# RPI_Pico_Breakout_2021-05-18.net
KiCad netlist of a schematic drawn in EasyEDA
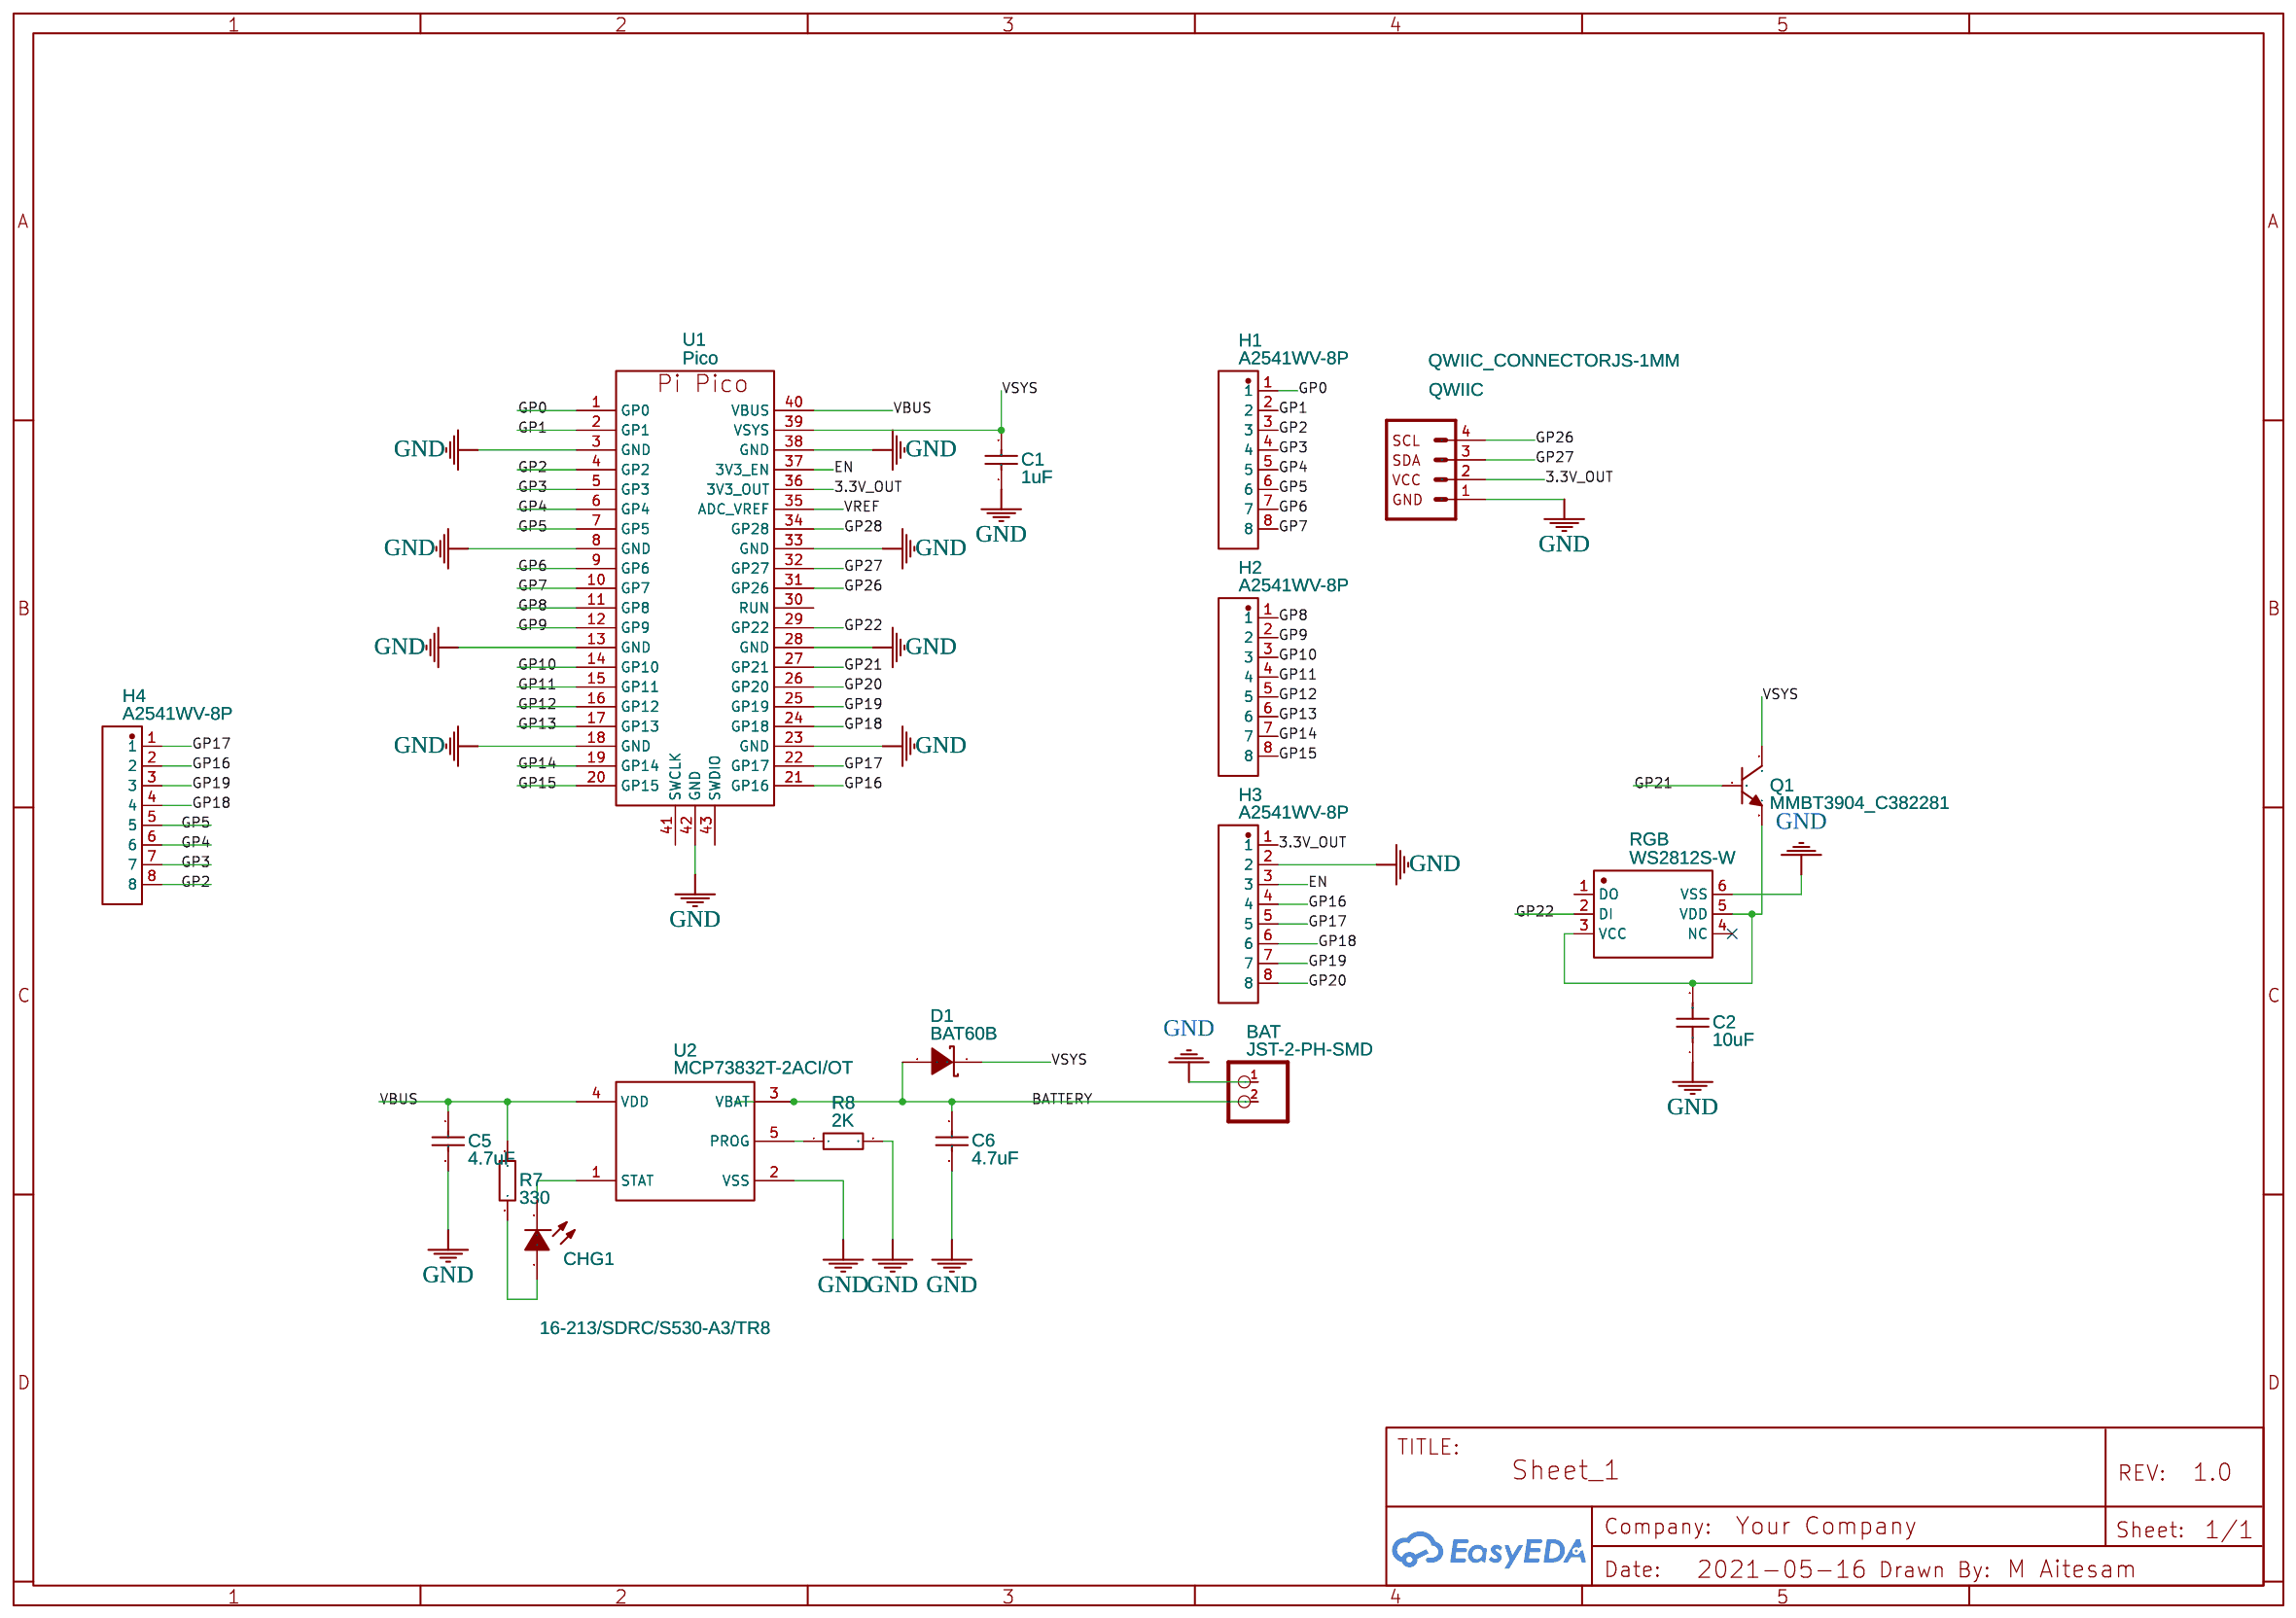
[diagram p0: schematic sheet]

(export (version "E")
  (design (tool "Eeschema 10.0.6"))
  (components
    (comp (ref "BAT") (value "JST-2-PH-SMD") (libsource (lib "") (part "JST-2-PH-SMD")))
    (comp (ref "C1")
      (value "1uF")
      (fields
        (field (name "BOM_Manufacturer Part") "CL05A105KP5NNNC")
        (field (name "BOM_Supplier Part") "C14445")
      )
      (libsource (lib "") (part "CL05A105KP5NNNC"))
    )
    (comp (ref "C2")
      (value "10uF")
      (fields
        (field (name "BOM_Manufacturer Part") "CL10A106KP8NNNC")
        (field (name "BOM_Supplier Part") "C19702")
      )
      (libsource (lib "") (part "CL10A106KP8NNNC"))
    )
    (comp (ref "C5")
      (value "4.7uF")
      (fields
        (field (name "BOM_Manufacturer Part") "CL21A475KAQNNNE")
        (field (name "BOM_Supplier Part") "C1779")
      )
      (libsource (lib "") (part "CL21A475KAQNNNE"))
    )
    (comp (ref "C6")
      (value "4.7uF")
      (fields
        (field (name "BOM_Manufacturer Part") "CL21A475KAQNNNE")
        (field (name "BOM_Supplier Part") "C1779")
      )
      (libsource (lib "") (part "CL21A475KAQNNNE"))
    )
    (comp (ref "CHG1")
      (value "16-213/SDRC/S530-A3/TR8")
      (fields (field (name "BOM_Supplier Part") "C71911"))
      (libsource (lib "") (part "16-213/SDRC/S530-A3/TR8"))
    )
    (comp (ref "D1")
      (value "BAT60B")
      (fields (field (name "BOM_Supplier Part") "C22638"))
      (libsource (lib "") (part "BAT60B"))
    )
    (comp (ref "H1")
      (value "A2541WV-8P")
      (fields (field (name "BOM_Supplier Part") "C225483"))
      (libsource (lib "") (part "A2541WV-8P"))
    )
    (comp (ref "H2")
      (value "A2541WV-8P")
      (fields (field (name "BOM_Supplier Part") "C225483"))
      (libsource (lib "") (part "A2541WV-8P"))
    )
    (comp (ref "H3")
      (value "A2541WV-8P")
      (fields (field (name "BOM_Supplier Part") "C225483"))
      (libsource (lib "") (part "A2541WV-8P"))
    )
    (comp (ref "H4")
      (value "A2541WV-8P")
      (fields (field (name "BOM_Supplier Part") "C225483"))
      (libsource (lib "") (part "A2541WV-8P"))
    )
    (comp (ref "Q1")
      (value "MMBT3904_C382281")
      (fields (field (name "BOM_Manufacturer Part") "MMBT3904") (field (name "BOM_Supplier Part") "C382281"))
      (libsource (lib "") (part "MMBT3904_C382281"))
    )
    (comp (ref "QWIIC") (value "QWIIC_CONNECTORJS-1MM") (libsource (lib "") (part "QWIIC_CONNECTORJS-1MM")))
    (comp (ref "R7")
      (value "330")
      (fields
        (field (name "BOM_Manufacturer Part") "0402WGJ0331TCE")
        (field (name "BOM_Supplier Part") "C12246")
      )
      (libsource (lib "") (part "0402WGJ0331TCE"))
    )
    (comp (ref "R8")
      (value "2K")
      (fields
        (field (name "BOM_Manufacturer Part") "0402WGF2001TCE")
        (field (name "BOM_Supplier Part") "C4109")
      )
      (libsource (lib "") (part "0402WGF2001TCE"))
    )
    (comp (ref "RGB")
      (value "WS2812S-W")
      (fields (field (name "BOM_Supplier Part") "C114584"))
      (libsource (lib "") (part "WS2812S-W"))
    )
    (comp (ref "U1")
      (value "Pico")
      (fields (field (name "BOM_Manufacturer Part") "Pi Pico"))
      (libsource (lib "") (part "Pico"))
    )
    (comp (ref "U2")
      (value "MCP73832T-2ACI/OT")
      (fields (field (name "BOM_Supplier Part") "C38066"))
      (libsource (lib "") (part "MCP73832T-2ACI/OT"))
    )
  )
  (nets
    (net (code "1") (name "/3.3V_OUT") (class "Default")
      (node (ref "H3") (pin "1") (pinfunction "1_1") (pintype "unspecified"))
      (node (ref "QWIIC") (pin "2") (pinfunction "2_2") (pintype "bidirectional"))
      (node (ref "U1") (pin "36") (pinfunction "3V3_OUT_36") (pintype "unspecified"))
    )
    (net (code "2") (name "/BATTERY") (class "Default")
      (node (ref "BAT") (pin "2") (pinfunction "+_2") (pintype "unspecified"))
      (node (ref "C6") (pin "2") (pinfunction "2_2") (pintype "input"))
      (node (ref "D1") (pin "2") (pinfunction "A_2") (pintype "unspecified"))
      (node (ref "U2") (pin "3") (pinfunction "VBAT_3") (pintype "passive"))
    )
    (net (code "3") (name "/EN") (class "Default")
      (node (ref "H3") (pin "3") (pinfunction "3_3") (pintype "unspecified"))
      (node (ref "U1") (pin "37") (pinfunction "3V3_EN_37") (pintype "unspecified"))
    )
    (net (code "4") (name "/GP0") (class "Default")
      (node (ref "H1") (pin "1") (pinfunction "1_1") (pintype "unspecified"))
      (node (ref "U1") (pin "1") (pinfunction "GP0_1") (pintype "unspecified"))
    )
    (net (code "5") (name "/GP1") (class "Default")
      (node (ref "H1") (pin "2") (pinfunction "2_2") (pintype "unspecified"))
      (node (ref "U1") (pin "2") (pinfunction "GP1_2") (pintype "unspecified"))
    )
    (net (code "6") (name "/GP2") (class "Default")
      (node (ref "H1") (pin "3") (pinfunction "3_3") (pintype "unspecified"))
      (node (ref "H4") (pin "8") (pinfunction "8_8") (pintype "unspecified"))
      (node (ref "U1") (pin "4") (pinfunction "GP2_4") (pintype "unspecified"))
    )
    (net (code "7") (name "/GP3") (class "Default")
      (node (ref "H1") (pin "4") (pinfunction "4_4") (pintype "unspecified"))
      (node (ref "H4") (pin "7") (pinfunction "7_7") (pintype "unspecified"))
      (node (ref "U1") (pin "5") (pinfunction "GP3_5") (pintype "unspecified"))
    )
    (net (code "8") (name "/GP4") (class "Default")
      (node (ref "H1") (pin "5") (pinfunction "5_5") (pintype "unspecified"))
      (node (ref "H4") (pin "6") (pinfunction "6_6") (pintype "unspecified"))
      (node (ref "U1") (pin "6") (pinfunction "GP4_6") (pintype "unspecified"))
    )
    (net (code "9") (name "/GP5") (class "Default")
      (node (ref "H1") (pin "6") (pinfunction "6_6") (pintype "unspecified"))
      (node (ref "H4") (pin "5") (pinfunction "5_5") (pintype "unspecified"))
      (node (ref "U1") (pin "7") (pinfunction "GP5_7") (pintype "unspecified"))
    )
    (net (code "10") (name "/GP6") (class "Default")
      (node (ref "H1") (pin "7") (pinfunction "7_7") (pintype "unspecified"))
      (node (ref "U1") (pin "9") (pinfunction "GP6_9") (pintype "unspecified"))
    )
    (net (code "11") (name "/GP7") (class "Default")
      (node (ref "H1") (pin "8") (pinfunction "8_8") (pintype "unspecified"))
      (node (ref "U1") (pin "10") (pinfunction "GP7_10") (pintype "unspecified"))
    )
    (net (code "12") (name "/GP8") (class "Default")
      (node (ref "H2") (pin "1") (pinfunction "1_1") (pintype "unspecified"))
      (node (ref "U1") (pin "11") (pinfunction "GP8_11") (pintype "unspecified"))
    )
    (net (code "13") (name "/GP9") (class "Default")
      (node (ref "H2") (pin "2") (pinfunction "2_2") (pintype "unspecified"))
      (node (ref "U1") (pin "12") (pinfunction "GP9_12") (pintype "unspecified"))
    )
    (net (code "14") (name "/GP10") (class "Default")
      (node (ref "H2") (pin "3") (pinfunction "3_3") (pintype "unspecified"))
      (node (ref "U1") (pin "14") (pinfunction "GP10_14") (pintype "unspecified"))
    )
    (net (code "15") (name "/GP11") (class "Default")
      (node (ref "H2") (pin "4") (pinfunction "4_4") (pintype "unspecified"))
      (node (ref "U1") (pin "15") (pinfunction "GP11_15") (pintype "unspecified"))
    )
    (net (code "16") (name "/GP12") (class "Default")
      (node (ref "H2") (pin "5") (pinfunction "5_5") (pintype "unspecified"))
      (node (ref "U1") (pin "16") (pinfunction "GP12_16") (pintype "unspecified"))
    )
    (net (code "17") (name "/GP13") (class "Default")
      (node (ref "H2") (pin "6") (pinfunction "6_6") (pintype "unspecified"))
      (node (ref "U1") (pin "17") (pinfunction "GP13_17") (pintype "unspecified"))
    )
    (net (code "18") (name "/GP14") (class "Default")
      (node (ref "H2") (pin "7") (pinfunction "7_7") (pintype "unspecified"))
      (node (ref "U1") (pin "19") (pinfunction "GP14_19") (pintype "unspecified"))
    )
    (net (code "19") (name "/GP15") (class "Default")
      (node (ref "H2") (pin "8") (pinfunction "8_8") (pintype "unspecified"))
      (node (ref "U1") (pin "20") (pinfunction "GP15_20") (pintype "unspecified"))
    )
    (net (code "20") (name "/GP16") (class "Default")
      (node (ref "H3") (pin "4") (pinfunction "4_4") (pintype "unspecified"))
      (node (ref "H4") (pin "2") (pinfunction "2_2") (pintype "unspecified"))
      (node (ref "U1") (pin "21") (pinfunction "GP16_21") (pintype "unspecified"))
    )
    (net (code "21") (name "/GP17") (class "Default")
      (node (ref "H3") (pin "5") (pinfunction "5_5") (pintype "unspecified"))
      (node (ref "H4") (pin "1") (pinfunction "1_1") (pintype "unspecified"))
      (node (ref "U1") (pin "22") (pinfunction "GP17_22") (pintype "unspecified"))
    )
    (net (code "22") (name "/GP18") (class "Default")
      (node (ref "H3") (pin "6") (pinfunction "6_6") (pintype "unspecified"))
      (node (ref "H4") (pin "4") (pinfunction "4_4") (pintype "unspecified"))
      (node (ref "U1") (pin "24") (pinfunction "GP18_24") (pintype "unspecified"))
    )
    (net (code "23") (name "/GP19") (class "Default")
      (node (ref "H3") (pin "7") (pinfunction "7_7") (pintype "unspecified"))
      (node (ref "H4") (pin "3") (pinfunction "3_3") (pintype "unspecified"))
      (node (ref "U1") (pin "25") (pinfunction "GP19_25") (pintype "unspecified"))
    )
    (net (code "24") (name "/GP20") (class "Default")
      (node (ref "H3") (pin "8") (pinfunction "8_8") (pintype "unspecified"))
      (node (ref "U1") (pin "26") (pinfunction "GP20_26") (pintype "unspecified"))
    )
    (net (code "25") (name "/GP21") (class "Default")
      (node (ref "Q1") (pin "1") (pinfunction "B_1") (pintype "unspecified"))
      (node (ref "U1") (pin "27") (pinfunction "GP21_27") (pintype "unspecified"))
    )
    (net (code "26") (name "/GP22") (class "Default")
      (node (ref "RGB") (pin "2") (pinfunction "DI_2") (pintype "unspecified"))
      (node (ref "U1") (pin "29") (pinfunction "GP22_29") (pintype "unspecified"))
    )
    (net (code "27") (name "/GP26") (class "Default")
      (node (ref "QWIIC") (pin "4") (pinfunction "4_4") (pintype "bidirectional"))
      (node (ref "U1") (pin "31") (pinfunction "GP26_31") (pintype "unspecified"))
    )
    (net (code "28") (name "/GP27") (class "Default")
      (node (ref "QWIIC") (pin "3") (pinfunction "3_3") (pintype "bidirectional"))
      (node (ref "U1") (pin "32") (pinfunction "GP27_32") (pintype "unspecified"))
    )
    (net (code "29") (name "/GP28") (class "Default")
      (node (ref "U1") (pin "34") (pinfunction "GP28_34") (pintype "unspecified"))
    )
    (net (code "30") (name "/VBUS") (class "Default")
      (node (ref "C5") (pin "2") (pinfunction "2_2") (pintype "input"))
      (node (ref "R7") (pin "1") (pinfunction "1_1") (pintype "input"))
      (node (ref "U1") (pin "40") (pinfunction "VBUS_40") (pintype "unspecified"))
      (node (ref "U2") (pin "4") (pinfunction "VDD_4") (pintype "passive"))
    )
    (net (code "31") (name "/VREF") (class "Default")
      (node (ref "U1") (pin "35") (pinfunction "ADC_VREF_35") (pintype "unspecified"))
    )
    (net (code "32") (name "/VSYS") (class "Default")
      (node (ref "C1") (pin "2") (pinfunction "2_2") (pintype "input"))
      (node (ref "D1") (pin "1") (pinfunction "K_1") (pintype "unspecified"))
      (node (ref "Q1") (pin "3") (pinfunction "C_3") (pintype "unspecified"))
      (node (ref "U1") (pin "39") (pinfunction "VSYS_39") (pintype "unspecified"))
    )
    (net (code "33") (name "GND") (class "Default")
      (node (ref "BAT") (pin "1") (pinfunction "-_1") (pintype "unspecified"))
      (node (ref "C1") (pin "1") (pinfunction "1_1") (pintype "input"))
      (node (ref "C2") (pin "1") (pinfunction "1_1") (pintype "unspecified"))
      (node (ref "C5") (pin "1") (pinfunction "1_1") (pintype "input"))
      (node (ref "C6") (pin "1") (pinfunction "1_1") (pintype "input"))
      (node (ref "H3") (pin "2") (pinfunction "2_2") (pintype "unspecified"))
      (node (ref "QWIIC") (pin "1") (pinfunction "1_1") (pintype "bidirectional"))
      (node (ref "R8") (pin "2") (pinfunction "2_2") (pintype "input"))
      (node (ref "RGB") (pin "6") (pinfunction "VSS_6") (pintype "unspecified"))
      (node (ref "U1") (pin "13") (pinfunction "GND_13") (pintype "unspecified"))
      (node (ref "U1") (pin "18") (pinfunction "GND_18") (pintype "unspecified"))
      (node (ref "U1") (pin "23") (pinfunction "GND_23") (pintype "unspecified"))
      (node (ref "U1") (pin "28") (pinfunction "GND_28") (pintype "unspecified"))
      (node (ref "U1") (pin "3") (pinfunction "GND_3") (pintype "unspecified"))
      (node (ref "U1") (pin "33") (pinfunction "GND_33") (pintype "unspecified"))
      (node (ref "U1") (pin "38") (pinfunction "GND_38") (pintype "unspecified"))
      (node (ref "U1") (pin "42") (pinfunction "GND_42") (pintype "unspecified"))
      (node (ref "U1") (pin "8") (pinfunction "GND_8") (pintype "unspecified"))
      (node (ref "U2") (pin "2") (pinfunction "VSS_2") (pintype "passive"))
    )
    (net (code "34") (name "Net-(CHG1-+)") (class "Default")
      (node (ref "CHG1") (pin "2") (pinfunction "+_2") (pintype "input"))
      (node (ref "R7") (pin "2") (pinfunction "2_2") (pintype "input"))
    )
    (net (code "35") (name "Net-(CHG1--)") (class "Default")
      (node (ref "CHG1") (pin "1") (pinfunction "-_1") (pintype "input"))
      (node (ref "U2") (pin "1") (pinfunction "STAT_1") (pintype "unspecified"))
    )
    (net (code "36") (name "Net-(Q1-E)") (class "Default")
      (node (ref "C2") (pin "2") (pinfunction "2_2") (pintype "unspecified"))
      (node (ref "Q1") (pin "2") (pinfunction "E_2") (pintype "unspecified"))
      (node (ref "RGB") (pin "3") (pinfunction "VCC_3") (pintype "unspecified"))
      (node (ref "RGB") (pin "5") (pinfunction "VDD_5") (pintype "unspecified"))
    )
    (net (code "37") (name "Net-(U2-PROG)") (class "Default")
      (node (ref "R8") (pin "1") (pinfunction "1_1") (pintype "input"))
      (node (ref "U2") (pin "5") (pinfunction "PROG_5") (pintype "unspecified"))
    )
    (net (code "38") (name "unconnected-(RGB-DO-Pad1)") (class "Default")
      (node (ref "RGB") (pin "1") (pinfunction "DO_1") (pintype "unspecified"))
    )
    (net (code "39") (name "unconnected-(RGB-NC-Pad4)") (class "Default")
      (node (ref "RGB") (pin "4") (pinfunction "NC_4") (pintype "unspecified+no_connect"))
    )
    (net (code "40") (name "unconnected-(U1-RUN-Pad30)") (class "Default")
      (node (ref "U1") (pin "30") (pinfunction "RUN_30") (pintype "unspecified"))
    )
    (net (code "41") (name "unconnected-(U1-SWCLK-Pad41)") (class "Default")
      (node (ref "U1") (pin "41") (pinfunction "SWCLK_41") (pintype "unspecified"))
    )
    (net (code "42") (name "unconnected-(U1-SWDIO-Pad43)") (class "Default")
      (node (ref "U1") (pin "43") (pinfunction "SWDIO_43") (pintype "unspecified"))
    )
  )
)
